# GPSDO.net
KiCad netlist of a schematic drawn in Altium Designer
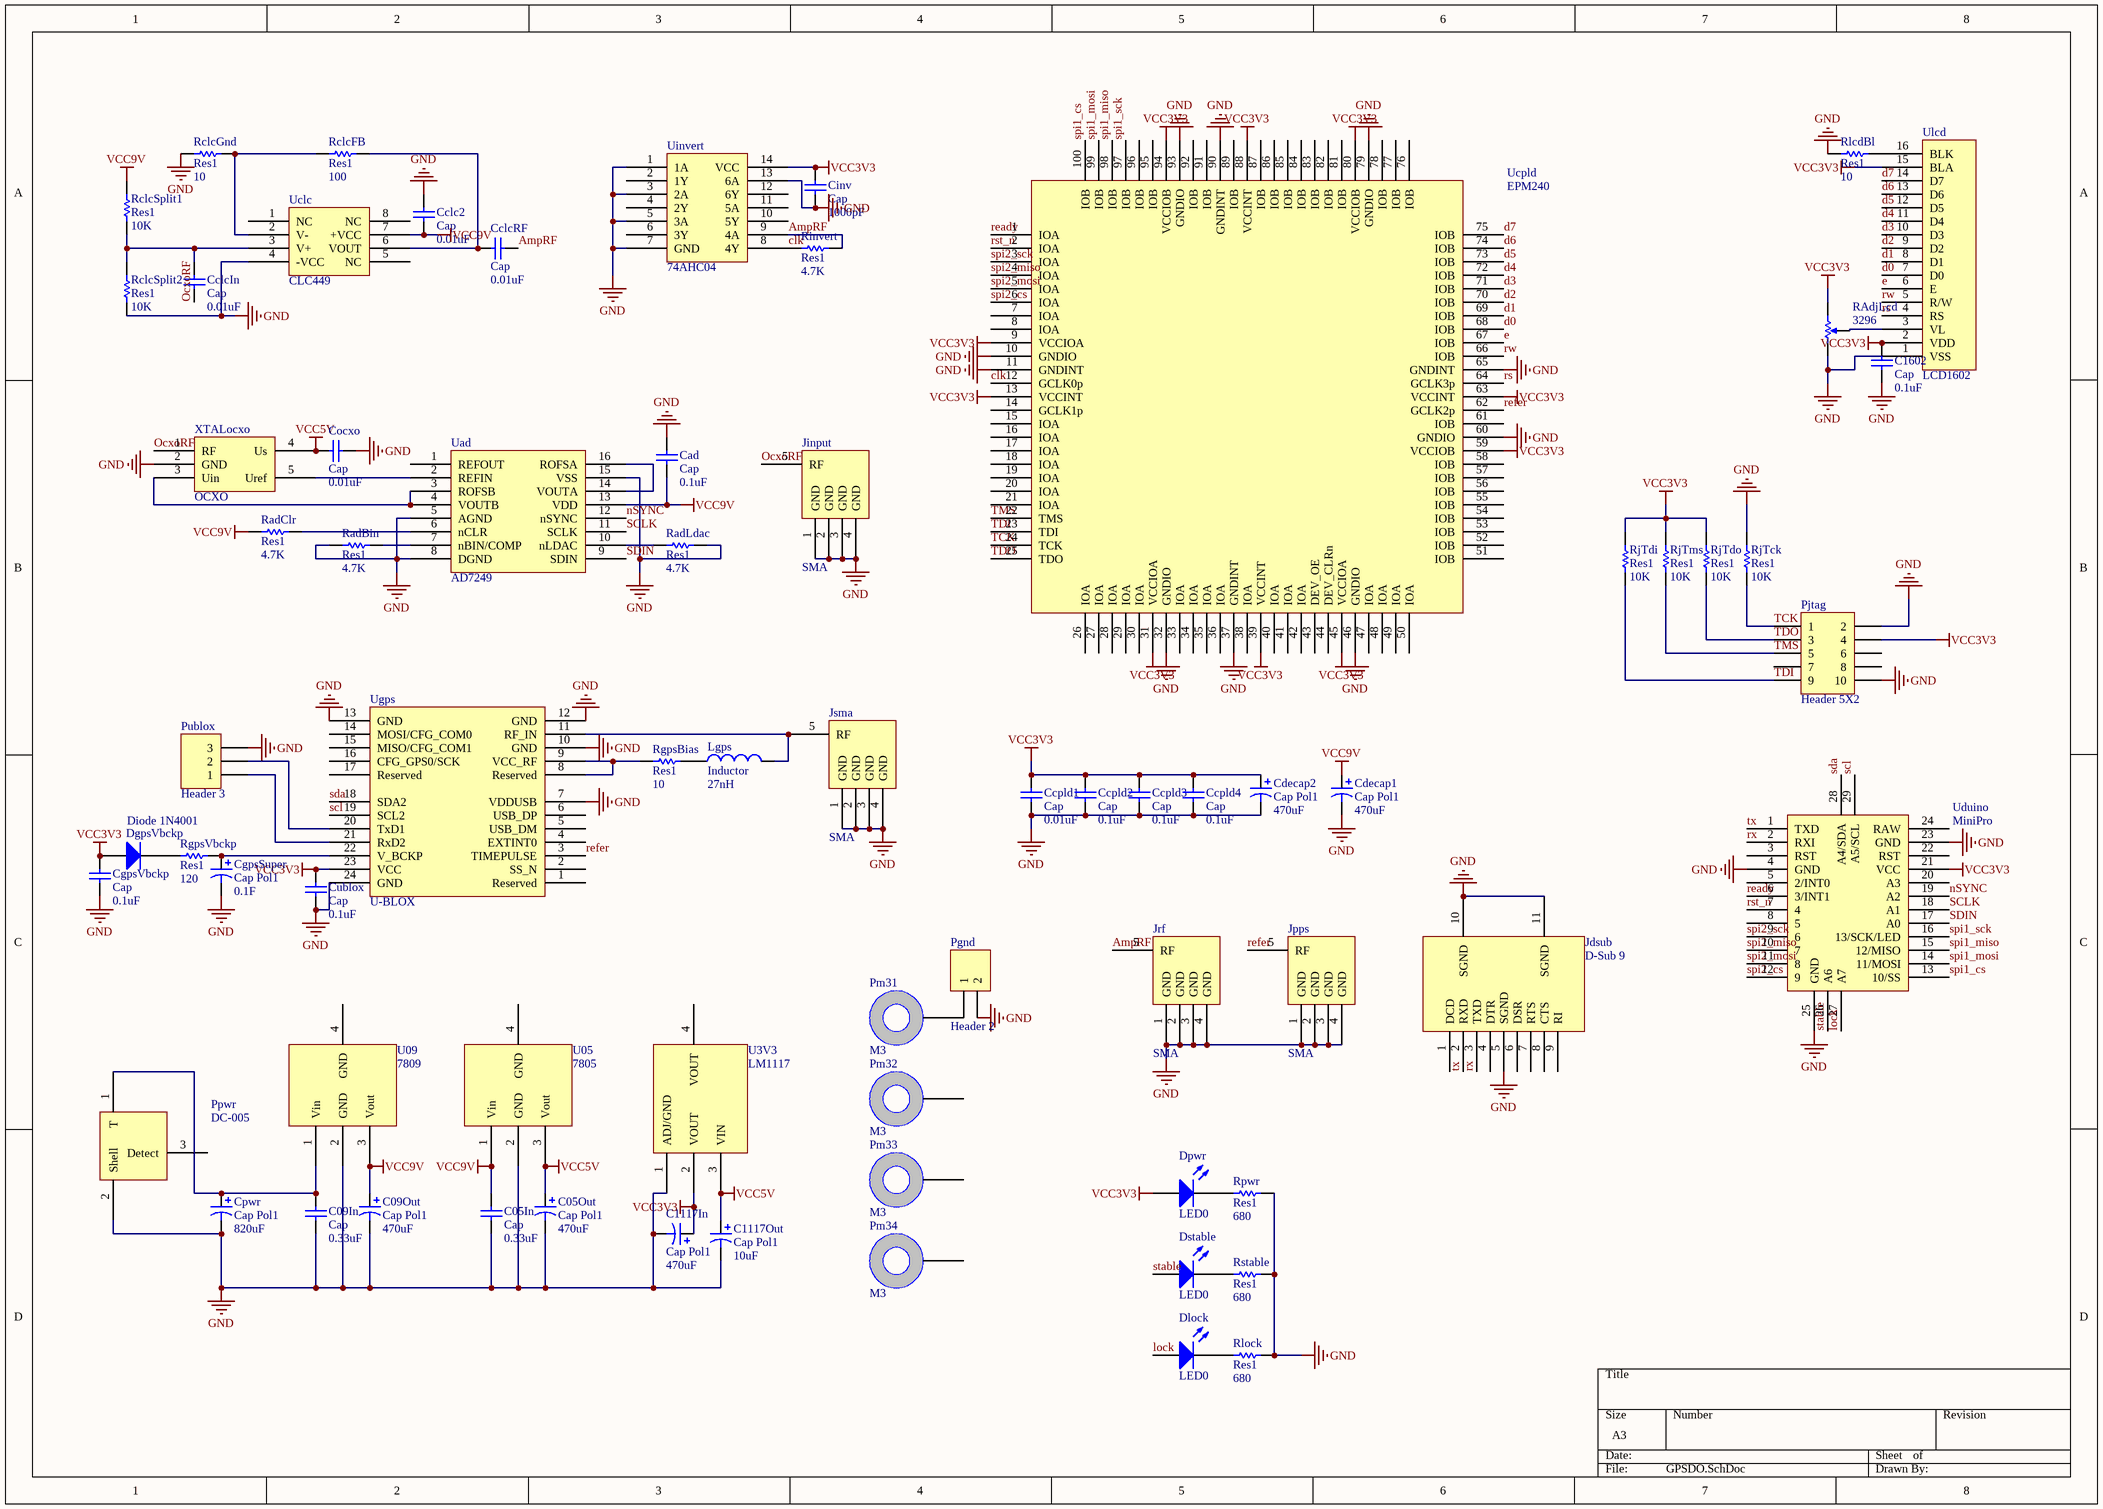
[diagram p0: GPSDO.SchDoc]

(export (version "E")
  (design (tool "Eeschema 10.0.6"))
  (components
    (comp (ref "C05In")
      (value "Cap")
      (footprint "ERO MKC1858 0.33uF/63V")
      (description "Capacitor")
      (fields (field (name "ALTIUM_VALUE") "0.33uF") (field (name "PUBLISHER") "Altium Limited"))
      (libsource (lib "Miscellaneous Devices") (part "Cap"))
    )
    (comp (ref "C05Out")
      (value "Cap Pol1")
      (footprint "SANYO SEP 560uF 10V")
      (description "Polarized Capacitor (Radial)")
      (fields (field (name "ALTIUM_VALUE") "470uF") (field (name "PUBLISHER") "Altium Limited"))
      (libsource (lib "Miscellaneous Devices") (part "Cap Pol1"))
    )
    (comp (ref "C09In")
      (value "Cap")
      (footprint "ERO MKC1858 0.33uF/63V")
      (description "Capacitor")
      (fields (field (name "ALTIUM_VALUE") "0.33uF") (field (name "PUBLISHER") "Altium Limited"))
      (libsource (lib "Miscellaneous Devices") (part "Cap"))
    )
    (comp (ref "C09Out")
      (value "Cap Pol1")
      (footprint "SANYO SEP 560uF 10V")
      (description "Polarized Capacitor (Radial)")
      (fields (field (name "ALTIUM_VALUE") "470uF") (field (name "PUBLISHER") "Altium Limited"))
      (libsource (lib "Miscellaneous Devices") (part "Cap Pol1"))
    )
    (comp (ref "C1117In")
      (value "Cap Pol1")
      (footprint "SANYO SEP 560uF 10V")
      (description "Polarized Capacitor (Radial)")
      (fields (field (name "ALTIUM_VALUE") "470uF") (field (name "PUBLISHER") "Altium Limited"))
      (libsource (lib "Miscellaneous Devices") (part "Cap Pol1"))
    )
    (comp (ref "C1117Out")
      (value "Cap Pol1")
      (footprint "Nichicon FW 10uF 100V")
      (description "Polarized Capacitor (Radial)")
      (fields (field (name "ALTIUM_VALUE") "10uF") (field (name "PUBLISHER") "Altium Limited"))
      (libsource (lib "Miscellaneous Devices") (part "Cap Pol1"))
    )
    (comp (ref "C1602")
      (value "Cap")
      (footprint "BC MKT370 0.1uF/63V")
      (description "Capacitor")
      (fields (field (name "ALTIUM_VALUE") "0.1uF") (field (name "PUBLISHER") "Altium Limited"))
      (libsource (lib "Miscellaneous Devices") (part "Cap"))
    )
    (comp (ref "Cad")
      (value "Cap")
      (footprint "BC MKT370 0.1uF/63V")
      (description "Capacitor")
      (fields (field (name "ALTIUM_VALUE") "0.1uF") (field (name "PUBLISHER") "Altium Limited"))
      (libsource (lib "Miscellaneous Devices") (part "Cap"))
    )
    (comp (ref "Cclc2")
      (value "Cap")
      (footprint "BC MKT370 0.1uF/63V")
      (description "Capacitor")
      (fields (field (name "ALTIUM_VALUE") "0.01uF") (field (name "PUBLISHER") "Altium Limited"))
      (libsource (lib "Miscellaneous Devices") (part "Cap"))
    )
    (comp (ref "CclcIn")
      (value "Cap")
      (footprint "0805.Cap.L")
      (description "Capacitor")
      (fields (field (name "ALTIUM_VALUE") "0.01uF") (field (name "PUBLISHER") "Altium Limited"))
      (libsource (lib "Miscellaneous Devices") (part "Cap"))
    )
    (comp (ref "CclcRF")
      (value "Cap")
      (footprint "0805.Cap.L")
      (description "Capacitor")
      (fields (field (name "ALTIUM_VALUE") "0.01uF") (field (name "PUBLISHER") "Altium Limited"))
      (libsource (lib "Miscellaneous Devices") (part "Cap"))
    )
    (comp (ref "Ccpld1")
      (value "Cap")
      (footprint "BC MKT370 0.1uF/63V")
      (description "Capacitor")
      (fields (field (name "ALTIUM_VALUE") "0.01uF") (field (name "PUBLISHER") "Altium Limited"))
      (libsource (lib "Miscellaneous Devices") (part "Cap"))
    )
    (comp (ref "Ccpld2")
      (value "Cap")
      (footprint "BC MKT370 0.1uF/63V")
      (description "Capacitor")
      (fields (field (name "ALTIUM_VALUE") "0.1uF") (field (name "PUBLISHER") "Altium Limited"))
      (libsource (lib "Miscellaneous Devices") (part "Cap"))
    )
    (comp (ref "Ccpld3")
      (value "Cap")
      (footprint "BC MKT370 0.1uF/63V")
      (description "Capacitor")
      (fields (field (name "ALTIUM_VALUE") "0.1uF") (field (name "PUBLISHER") "Altium Limited"))
      (libsource (lib "Miscellaneous Devices") (part "Cap"))
    )
    (comp (ref "Ccpld4")
      (value "Cap")
      (footprint "BC MKT370 0.1uF/63V")
      (description "Capacitor")
      (fields (field (name "ALTIUM_VALUE") "0.1uF") (field (name "PUBLISHER") "Altium Limited"))
      (libsource (lib "Miscellaneous Devices") (part "Cap"))
    )
    (comp (ref "Cdecap1")
      (value "Cap Pol1")
      (footprint "SANYO SEP 560uF 10V")
      (description "Polarized Capacitor (Radial)")
      (fields (field (name "ALTIUM_VALUE") "470uF") (field (name "PUBLISHER") "Altium Limited"))
      (libsource (lib "Miscellaneous Devices") (part "Cap Pol1"))
    )
    (comp (ref "Cdecap2")
      (value "Cap Pol1")
      (footprint "SANYO SEP 560uF 10V")
      (description "Polarized Capacitor (Radial)")
      (fields (field (name "ALTIUM_VALUE") "470uF") (field (name "PUBLISHER") "Altium Limited"))
      (libsource (lib "Miscellaneous Devices") (part "Cap Pol1"))
    )
    (comp (ref "CgpsSuper")
      (value "Cap Pol1")
      (footprint "Panasonic SD 0.1F / 5.5V")
      (description "Polarized Capacitor (Radial)")
      (fields (field (name "ALTIUM_VALUE") "0.1F") (field (name "PUBLISHER") "Altium Limited"))
      (libsource (lib "Miscellaneous Devices") (part "Cap Pol1"))
    )
    (comp (ref "CgpsVbckp")
      (value "Cap")
      (footprint "BC MKT370 0.1uF/63V")
      (description "Capacitor")
      (fields (field (name "ALTIUM_VALUE") "0.1uF") (field (name "PUBLISHER") "Altium Limited"))
      (libsource (lib "Miscellaneous Devices") (part "Cap"))
    )
    (comp (ref "Cinv")
      (value "Cap")
      (footprint "0805.Cap.L")
      (description "Capacitor")
      (fields (field (name "ALTIUM_VALUE") "1000pF") (field (name "PUBLISHER") "Altium Limited"))
      (libsource (lib "Miscellaneous Devices") (part "Cap"))
    )
    (comp (ref "Cocxo")
      (value "Cap")
      (footprint "BC MKT370 0.1uF/63V")
      (description "Capacitor")
      (fields (field (name "ALTIUM_VALUE") "0.01uF") (field (name "PUBLISHER") "Altium Limited"))
      (libsource (lib "Miscellaneous Devices") (part "Cap"))
    )
    (comp (ref "Cpwr")
      (value "Cap Pol1")
      (footprint "NCC LXZ 820uF 25V")
      (description "Polarized Capacitor (Radial)")
      (fields (field (name "ALTIUM_VALUE") "820uF") (field (name "PUBLISHER") "Altium Limited"))
      (libsource (lib "Miscellaneous Devices") (part "Cap Pol1"))
    )
    (comp (ref "Cublox")
      (value "Cap")
      (footprint "BC MKT370 0.1uF/63V")
      (description "Capacitor")
      (fields (field (name "ALTIUM_VALUE") "0.1uF") (field (name "PUBLISHER") "Altium Limited"))
      (libsource (lib "Miscellaneous Devices") (part "Cap"))
    )
    (comp (ref "DgpsVbckp")
      (value "Diode 1N4001")
      (footprint "1N4007")
      (description "1 Amp General Purpose Rectifier")
      (fields (field (name "PUBLISHER") "Altium Limited"))
      (libsource (lib "Miscellaneous Devices") (part "Diode 1N4001"))
    )
    (comp (ref "Dlock")
      (value "LED0")
      (footprint "3mm LED")
      (description "Typical INFRARED GaAs LED")
      (fields (field (name "PUBLISHER") "Altium Limited"))
      (libsource (lib "Miscellaneous Devices") (part "LED0"))
    )
    (comp (ref "Dpwr")
      (value "LED0")
      (footprint "3mm LED")
      (description "Typical INFRARED GaAs LED")
      (fields (field (name "PUBLISHER") "Altium Limited"))
      (libsource (lib "Miscellaneous Devices") (part "LED0"))
    )
    (comp (ref "Dstable")
      (value "LED0")
      (footprint "3mm LED")
      (description "Typical INFRARED GaAs LED")
      (fields (field (name "PUBLISHER") "Altium Limited"))
      (libsource (lib "Miscellaneous Devices") (part "LED0"))
    )
    (comp (ref "Jdsub") (value "D-Sub 9") (footprint "DSUB-9") (libsource (lib "Connector") (part "D-Sub 9")))
    (comp (ref "Jinput") (value "SMA") (footprint "SMA") (libsource (lib "Connector") (part "SMA")))
    (comp (ref "Jpps") (value "SMA") (footprint "SMA") (libsource (lib "Connector") (part "SMA")))
    (comp (ref "Jrf") (value "SMA") (footprint "SMA") (libsource (lib "Connector") (part "SMA")))
    (comp (ref "Jsma") (value "SMA") (footprint "SMA") (libsource (lib "Connector") (part "SMA")))
    (comp (ref "Lgps")
      (value "Inductor")
      (footprint "0805.L.L")
      (fields (field (name "ALTIUM_VALUE") "27nH") (field (name "PUBLISHER") "Altium Limited"))
      (libsource (lib "Miscellaneous Devices") (part "Inductor"))
    )
    (comp (ref "Pgnd")
      (value "Header 2")
      (footprint "HDR1X2")
      (description "Header, 2-Pin")
      (fields (field (name "PUBLISHER") "Altium Limited"))
      (libsource (lib "Miscellaneous Connectors") (part "Header 2"))
    )
    (comp (ref "Pjtag")
      (value "Header 5X2")
      (footprint "DC3 2.54mm 10P")
      (description "Header, 5-Pin, Dual row")
      (fields (field (name "PUBLISHER") "Altium Limited"))
      (libsource (lib "Miscellaneous Connectors") (part "Header 5X2"))
    )
    (comp (ref "Pm31")
      (value "M3")
      (footprint "M3 Screw Mount")
      (description "M3 screw mount, hole d: 3.5mm")
      (libsource (lib "TPA6120A2") (part "M3 Screw Mount"))
    )
    (comp (ref "Pm32")
      (value "M3")
      (footprint "M3 Screw Mount")
      (description "M3 screw mount, hole d: 3.5mm")
      (libsource (lib "TPA6120A2") (part "M3 Screw Mount"))
    )
    (comp (ref "Pm33")
      (value "M3")
      (footprint "M3 Screw Mount")
      (description "M3 screw mount, hole d: 3.5mm")
      (libsource (lib "TPA6120A2") (part "M3 Screw Mount"))
    )
    (comp (ref "Pm34")
      (value "M3")
      (footprint "M3 Screw Mount")
      (description "M3 screw mount, hole d: 3.5mm")
      (libsource (lib "TPA6120A2") (part "M3 Screw Mount"))
    )
    (comp (ref "Ppwr") (value "DC-005") (footprint "DC-005") (libsource (lib "Connector") (part "DC-005")))
    (comp (ref "Publox")
      (value "Header 3")
      (footprint "HDR1X3")
      (description "Header, 3-Pin")
      (fields (field (name "PUBLISHER") "Altium Limited"))
      (libsource (lib "Miscellaneous Connectors") (part "Header 3"))
    )
    (comp (ref "RadBin")
      (value "Res1")
      (footprint "RJ24")
      (description "Resistor")
      (fields (field (name "ALTIUM_VALUE") "4.7K") (field (name "PUBLISHER") "Altium Limited"))
      (libsource (lib "Miscellaneous Devices") (part "Res1"))
    )
    (comp (ref "RadClr")
      (value "Res1")
      (footprint "RJ24")
      (description "Resistor")
      (fields (field (name "ALTIUM_VALUE") "4.7K") (field (name "PUBLISHER") "Altium Limited"))
      (libsource (lib "Miscellaneous Devices") (part "Res1"))
    )
    (comp (ref "RAdjLcd")
      (value "3296")
      (footprint "3296W")
      (description "3296 - 3/8\" Square Trimming Potentiometer")
      (libsource (lib "DAC") (part "Trimming Potentiometer"))
    )
    (comp (ref "RadLdac")
      (value "Res1")
      (footprint "RJ24")
      (description "Resistor")
      (fields (field (name "ALTIUM_VALUE") "4.7K") (field (name "PUBLISHER") "Altium Limited"))
      (libsource (lib "Miscellaneous Devices") (part "Res1"))
    )
    (comp (ref "RclcFB")
      (value "Res1")
      (footprint "0805.Res.L")
      (description "Resistor")
      (fields (field (name "ALTIUM_VALUE") "100") (field (name "PUBLISHER") "Altium Limited"))
      (libsource (lib "Miscellaneous Devices") (part "Res1"))
    )
    (comp (ref "RclcGnd")
      (value "Res1")
      (footprint "0805.Res.L")
      (description "Resistor")
      (fields (field (name "ALTIUM_VALUE") "10") (field (name "PUBLISHER") "Altium Limited"))
      (libsource (lib "Miscellaneous Devices") (part "Res1"))
    )
    (comp (ref "RclcSplit1")
      (value "Res1")
      (footprint "0805.Res.L")
      (description "Resistor")
      (fields (field (name "ALTIUM_VALUE") "10K") (field (name "PUBLISHER") "Altium Limited"))
      (libsource (lib "Miscellaneous Devices") (part "Res1"))
    )
    (comp (ref "RclcSplit2")
      (value "Res1")
      (footprint "0805.Res.L")
      (description "Resistor")
      (fields (field (name "ALTIUM_VALUE") "10K") (field (name "PUBLISHER") "Altium Limited"))
      (libsource (lib "Miscellaneous Devices") (part "Res1"))
    )
    (comp (ref "RgpsBias")
      (value "Res1")
      (footprint "0805.Res.L")
      (description "Resistor")
      (fields (field (name "ALTIUM_VALUE") "10") (field (name "PUBLISHER") "Altium Limited"))
      (libsource (lib "Miscellaneous Devices") (part "Res1"))
    )
    (comp (ref "RgpsVbckp")
      (value "Res1")
      (footprint "RJ24")
      (description "Resistor")
      (fields (field (name "ALTIUM_VALUE") "120") (field (name "PUBLISHER") "Altium Limited"))
      (libsource (lib "Miscellaneous Devices") (part "Res1"))
    )
    (comp (ref "Rinvert")
      (value "Res1")
      (footprint "0805.Res.L")
      (description "Resistor")
      (fields (field (name "ALTIUM_VALUE") "4.7K") (field (name "PUBLISHER") "Altium Limited"))
      (libsource (lib "Miscellaneous Devices") (part "Res1"))
    )
    (comp (ref "RjTck")
      (value "Res1")
      (footprint "RJ24")
      (description "Resistor")
      (fields (field (name "ALTIUM_VALUE") "10K") (field (name "PUBLISHER") "Altium Limited"))
      (libsource (lib "Miscellaneous Devices") (part "Res1"))
    )
    (comp (ref "RjTdi")
      (value "Res1")
      (footprint "RJ24")
      (description "Resistor")
      (fields (field (name "ALTIUM_VALUE") "10K") (field (name "PUBLISHER") "Altium Limited"))
      (libsource (lib "Miscellaneous Devices") (part "Res1"))
    )
    (comp (ref "RjTdo")
      (value "Res1")
      (footprint "RJ24")
      (description "Resistor")
      (fields (field (name "ALTIUM_VALUE") "10K") (field (name "PUBLISHER") "Altium Limited"))
      (libsource (lib "Miscellaneous Devices") (part "Res1"))
    )
    (comp (ref "RjTms")
      (value "Res1")
      (footprint "RJ24")
      (description "Resistor")
      (fields (field (name "ALTIUM_VALUE") "10K") (field (name "PUBLISHER") "Altium Limited"))
      (libsource (lib "Miscellaneous Devices") (part "Res1"))
    )
    (comp (ref "RlcdBl")
      (value "Res1")
      (footprint "RJ24")
      (description "Resistor")
      (fields (field (name "ALTIUM_VALUE") "10") (field (name "PUBLISHER") "Altium Limited"))
      (libsource (lib "Miscellaneous Devices") (part "Res1"))
    )
    (comp (ref "Rlock")
      (value "Res1")
      (footprint "RJ24")
      (description "Resistor")
      (fields (field (name "ALTIUM_VALUE") "680") (field (name "PUBLISHER") "Altium Limited"))
      (libsource (lib "Miscellaneous Devices") (part "Res1"))
    )
    (comp (ref "Rpwr")
      (value "Res1")
      (footprint "RJ24")
      (description "Resistor")
      (fields (field (name "ALTIUM_VALUE") "680") (field (name "PUBLISHER") "Altium Limited"))
      (libsource (lib "Miscellaneous Devices") (part "Res1"))
    )
    (comp (ref "Rstable")
      (value "Res1")
      (footprint "RJ24")
      (description "Resistor")
      (fields (field (name "ALTIUM_VALUE") "680") (field (name "PUBLISHER") "Altium Limited"))
      (libsource (lib "Miscellaneous Devices") (part "Res1"))
    )
    (comp (ref "U3V3")
      (value "LM1117")
      (footprint "LM1117 SOT-223")
      (description "LM1117-N/LM1117I 800mA Low-Dropout Linear Regulator")
      (libsource (lib "Power") (part "LM1117"))
    )
    (comp (ref "U05")
      (value "7805")
      (footprint "MC7805")
      (description "1.0 A Positive Voltage  Regulators")
      (libsource (lib "Power") (part "MC7805"))
    )
    (comp (ref "U09")
      (value "7809")
      (footprint "MC7805")
      (description "1.0 A Positive Voltage  Regulators")
      (libsource (lib "Power") (part "MC7805"))
    )
    (comp (ref "Uad")
      (value "AD7249")
      (footprint "AD7249 SOIC-16")
      (description "LC2MOS Dual 12-Bit Serial DACPORT")
      (libsource (lib "Chip") (part "AD7249"))
    )
    (comp (ref "Uclc")
      (value "CLC449")
      (footprint "CLC449 SOIC-8")
      (description "1.1GHz Ultra Wideband Monolithic Op Amp")
      (libsource (lib "Chip") (part "CLC449"))
    )
    (comp (ref "Ucpld")
      (value "EPM240")
      (footprint "EPM240/570 TQFP-100")
      (description "Altera Max II CPLD")
      (libsource (lib "Chip") (part "EPM240"))
    )
    (comp (ref "Uduino")
      (value "MiniPro")
      (footprint "DIP24 - Arduino")
      (description "Microcontroller board based on the ATmega328P")
      (libsource (lib "CS4398") (part "ArduinoMiniPro"))
    )
    (comp (ref "Ugps")
      (value "U-BLOX")
      (footprint "NEO-GPS")
      (description "u-blox 6 GPS Modules")
      (libsource (lib "Module") (part "NEO-GPS"))
    )
    (comp (ref "Uinvert")
      (value "74AHC04")
      (footprint "74AHC04 SOP-14")
      (description "hex inverter")
      (libsource (lib "Chip") (part "74AHC04"))
    )
    (comp (ref "Ulcd") (value "LCD1602") (footprint "LCD1602") (libsource (lib "Module") (part "LCD1602")))
    (comp (ref "XTALocxo") (value "OCXO") (footprint "MV85") (libsource (lib "Chip") (part "OCXO")))
  )
  (nets
    (net (code "1") (name "/AmpRF") (class "Default")
      (node (ref "CclcRF") (pin "2") (pinfunction "2_2") (pintype "passive"))
      (node (ref "Jrf") (pin "5") (pinfunction "RF_5") (pintype "passive"))
      (node (ref "Rinvert") (pin "2") (pinfunction "2_2") (pintype "passive"))
      (node (ref "Uinvert") (pin "9") (pinfunction "4A_9") (pintype "passive"))
    )
    (net (code "2") (name "/OcxoRF") (class "Default")
      (node (ref "CclcIn") (pin "1") (pinfunction "1_1") (pintype "passive"))
      (node (ref "Jinput") (pin "5") (pinfunction "RF_5") (pintype "passive"))
      (node (ref "XTALocxo") (pin "1") (pinfunction "RF_1") (pintype "passive"))
    )
    (net (code "3") (name "/SCLK") (class "Default")
      (node (ref "Uad") (pin "11") (pinfunction "SCLK_11") (pintype "passive"))
      (node (ref "Uduino") (pin "18") (pinfunction "A1_18") (pintype "passive"))
    )
    (net (code "4") (name "/SDIN") (class "Default")
      (node (ref "Uad") (pin "9") (pinfunction "SDIN_9") (pintype "passive"))
      (node (ref "Uduino") (pin "17") (pinfunction "A0_17") (pintype "passive"))
    )
    (net (code "5") (name "/TCK") (class "Default")
      (node (ref "Pjtag") (pin "1") (pinfunction "1_1") (pintype "passive"))
      (node (ref "RjTck") (pin "1") (pinfunction "1_1") (pintype "passive"))
      (node (ref "Ucpld") (pin "24") (pinfunction "TCK_24") (pintype "passive"))
    )
    (net (code "6") (name "/TDI") (class "Default")
      (node (ref "Pjtag") (pin "9") (pinfunction "9_9") (pintype "passive"))
      (node (ref "RjTdi") (pin "1") (pinfunction "1_1") (pintype "passive"))
      (node (ref "Ucpld") (pin "23") (pinfunction "TDI_23") (pintype "passive"))
    )
    (net (code "7") (name "/TDO") (class "Default")
      (node (ref "Pjtag") (pin "3") (pinfunction "3_3") (pintype "passive"))
      (node (ref "RjTdo") (pin "1") (pinfunction "1_1") (pintype "passive"))
      (node (ref "Ucpld") (pin "25") (pinfunction "TDO_25") (pintype "passive"))
    )
    (net (code "8") (name "/TMS") (class "Default")
      (node (ref "Pjtag") (pin "5") (pinfunction "5_5") (pintype "passive"))
      (node (ref "RjTms") (pin "1") (pinfunction "1_1") (pintype "passive"))
      (node (ref "Ucpld") (pin "22") (pinfunction "TMS_22") (pintype "passive"))
    )
    (net (code "9") (name "/clk") (class "Default")
      (node (ref "Rinvert") (pin "1") (pinfunction "1_1") (pintype "passive"))
      (node (ref "Ucpld") (pin "12") (pinfunction "GCLK0p_12") (pintype "passive"))
      (node (ref "Uinvert") (pin "8") (pinfunction "4Y_8") (pintype "passive"))
    )
    (net (code "10") (name "/d0") (class "Default")
      (node (ref "Ucpld") (pin "68") (pinfunction "IOB_68") (pintype "passive"))
      (node (ref "Ulcd") (pin "7") (pinfunction "D0_7") (pintype "passive"))
    )
    (net (code "11") (name "/d1") (class "Default")
      (node (ref "Ucpld") (pin "69") (pinfunction "IOB_69") (pintype "passive"))
      (node (ref "Ulcd") (pin "8") (pinfunction "D1_8") (pintype "passive"))
    )
    (net (code "12") (name "/d2") (class "Default")
      (node (ref "Ucpld") (pin "70") (pinfunction "IOB_70") (pintype "passive"))
      (node (ref "Ulcd") (pin "9") (pinfunction "D2_9") (pintype "passive"))
    )
    (net (code "13") (name "/d3") (class "Default")
      (node (ref "Ucpld") (pin "71") (pinfunction "IOB_71") (pintype "passive"))
      (node (ref "Ulcd") (pin "10") (pinfunction "D3_10") (pintype "passive"))
    )
    (net (code "14") (name "/d4") (class "Default")
      (node (ref "Ucpld") (pin "72") (pinfunction "IOB_72") (pintype "passive"))
      (node (ref "Ulcd") (pin "11") (pinfunction "D4_11") (pintype "passive"))
    )
    (net (code "15") (name "/d5") (class "Default")
      (node (ref "Ucpld") (pin "73") (pinfunction "IOB_73") (pintype "passive"))
      (node (ref "Ulcd") (pin "12") (pinfunction "D5_12") (pintype "passive"))
    )
    (net (code "16") (name "/d6") (class "Default")
      (node (ref "Ucpld") (pin "74") (pinfunction "IOB_74") (pintype "passive"))
      (node (ref "Ulcd") (pin "13") (pinfunction "D6_13") (pintype "passive"))
    )
    (net (code "17") (name "/d7") (class "Default")
      (node (ref "Ucpld") (pin "75") (pinfunction "IOB_75") (pintype "passive"))
      (node (ref "Ulcd") (pin "14") (pinfunction "D7_14") (pintype "passive"))
    )
    (net (code "18") (name "/e") (class "Default")
      (node (ref "Ucpld") (pin "67") (pinfunction "IOB_67") (pintype "passive"))
      (node (ref "Ulcd") (pin "6") (pinfunction "E_6") (pintype "passive"))
    )
    (net (code "19") (name "/lock") (class "Default")
      (node (ref "Dlock") (pin "1") (pinfunction "A_1") (pintype "passive"))
      (node (ref "Uduino") (pin "27") (pinfunction "A7_27") (pintype "passive"))
    )
    (net (code "20") (name "/nSYNC") (class "Default")
      (node (ref "Uad") (pin "12") (pinfunction "nSYNC_12") (pintype "passive"))
      (node (ref "Uduino") (pin "19") (pinfunction "A2_19") (pintype "passive"))
    )
    (net (code "21") (name "/ready") (class "Default")
      (node (ref "Ucpld") (pin "1") (pinfunction "IOA_1") (pintype "passive"))
      (node (ref "Uduino") (pin "6") (pinfunction "3/INT1_6") (pintype "passive"))
    )
    (net (code "22") (name "/refer") (class "Default")
      (node (ref "Jpps") (pin "5") (pinfunction "RF_5") (pintype "passive"))
      (node (ref "Ucpld") (pin "62") (pinfunction "GCLK2p_62") (pintype "passive"))
      (node (ref "Ugps") (pin "3") (pinfunction "TIMEPULSE_3") (pintype "passive"))
    )
    (net (code "23") (name "/rs") (class "Default")
      (node (ref "Ucpld") (pin "64") (pinfunction "GCLK3p_64") (pintype "passive"))
      (node (ref "Ulcd") (pin "4") (pinfunction "RS_4") (pintype "passive"))
    )
    (net (code "24") (name "/rst_n") (class "Default")
      (node (ref "Ucpld") (pin "2") (pinfunction "IOA_2") (pintype "passive"))
      (node (ref "Uduino") (pin "7") (pinfunction "4_7") (pintype "passive"))
    )
    (net (code "25") (name "/rw") (class "Default")
      (node (ref "Ucpld") (pin "66") (pinfunction "IOB_66") (pintype "passive"))
      (node (ref "Ulcd") (pin "5") (pinfunction "R/W_5") (pintype "passive"))
    )
    (net (code "26") (name "/rx") (class "Default")
      (node (ref "Jdsub") (pin "3") (pinfunction "TXD_3") (pintype "passive"))
      (node (ref "Uduino") (pin "2") (pinfunction "RXI_2") (pintype "passive"))
    )
    (net (code "27") (name "/scl") (class "Default")
      (node (ref "Uduino") (pin "29") (pinfunction "A5/SCL_29") (pintype "passive"))
      (node (ref "Ugps") (pin "19") (pinfunction "SCL2_19") (pintype "passive"))
    )
    (net (code "28") (name "/sda") (class "Default")
      (node (ref "Uduino") (pin "28") (pinfunction "A4/SDA_28") (pintype "passive"))
      (node (ref "Ugps") (pin "18") (pinfunction "SDA2_18") (pintype "passive"))
    )
    (net (code "29") (name "/spi1_cs") (class "Default")
      (node (ref "Ucpld") (pin "100") (pinfunction "IOB_100") (pintype "passive"))
      (node (ref "Uduino") (pin "13") (pinfunction "10/SS_13") (pintype "passive"))
    )
    (net (code "30") (name "/spi1_miso") (class "Default")
      (node (ref "Ucpld") (pin "98") (pinfunction "IOB_98") (pintype "passive"))
      (node (ref "Uduino") (pin "15") (pinfunction "12/MISO_15") (pintype "passive"))
    )
    (net (code "31") (name "/spi1_mosi") (class "Default")
      (node (ref "Ucpld") (pin "99") (pinfunction "IOB_99") (pintype "passive"))
      (node (ref "Uduino") (pin "14") (pinfunction "11/MOSI_14") (pintype "passive"))
    )
    (net (code "32") (name "/spi1_sck") (class "Default")
      (node (ref "Ucpld") (pin "97") (pinfunction "IOB_97") (pintype "passive"))
      (node (ref "Uduino") (pin "16") (pinfunction "13/SCK/LED_16") (pintype "passive"))
    )
    (net (code "33") (name "/spi2_cs") (class "Default")
      (node (ref "Ucpld") (pin "6") (pinfunction "IOA_6") (pintype "passive"))
      (node (ref "Uduino") (pin "12") (pinfunction "9_12") (pintype "passive"))
    )
    (net (code "34") (name "/spi2_miso") (class "Default")
      (node (ref "Ucpld") (pin "4") (pinfunction "IOA_4") (pintype "passive"))
      (node (ref "Uduino") (pin "10") (pinfunction "7_10") (pintype "passive"))
    )
    (net (code "35") (name "/spi2_mosi") (class "Default")
      (node (ref "Ucpld") (pin "5") (pinfunction "IOA_5") (pintype "passive"))
      (node (ref "Uduino") (pin "11") (pinfunction "8_11") (pintype "passive"))
    )
    (net (code "36") (name "/spi2_sck") (class "Default")
      (node (ref "Ucpld") (pin "3") (pinfunction "IOA_3") (pintype "passive"))
      (node (ref "Uduino") (pin "9") (pinfunction "6_9") (pintype "passive"))
    )
    (net (code "37") (name "/stable") (class "Default")
      (node (ref "Dstable") (pin "1") (pinfunction "A_1") (pintype "passive"))
      (node (ref "Uduino") (pin "26") (pinfunction "A6_26") (pintype "passive"))
    )
    (net (code "38") (name "/tx") (class "Default")
      (node (ref "Jdsub") (pin "2") (pinfunction "RXD_2") (pintype "passive"))
      (node (ref "Uduino") (pin "1") (pinfunction "TXD_1") (pintype "passive"))
    )
    (net (code "39") (name "GND") (class "Default")
      (node (ref "C05In") (pin "2") (pinfunction "2_2") (pintype "passive"))
      (node (ref "C05Out") (pin "2") (pinfunction "2_2") (pintype "passive"))
      (node (ref "C09In") (pin "1") (pinfunction "1_1") (pintype "passive"))
      (node (ref "C09Out") (pin "2") (pinfunction "2_2") (pintype "passive"))
      (node (ref "C1117In") (pin "2") (pinfunction "2_2") (pintype "passive"))
      (node (ref "C1117Out") (pin "2") (pinfunction "2_2") (pintype "passive"))
      (node (ref "C1602") (pin "1") (pinfunction "1_1") (pintype "passive"))
      (node (ref "Cad") (pin "2") (pinfunction "2_2") (pintype "passive"))
      (node (ref "Cclc2") (pin "2") (pinfunction "2_2") (pintype "passive"))
      (node (ref "Ccpld1") (pin "1") (pinfunction "1_1") (pintype "passive"))
      (node (ref "Ccpld2") (pin "1") (pinfunction "1_1") (pintype "passive"))
      (node (ref "Ccpld3") (pin "1") (pinfunction "1_1") (pintype "passive"))
      (node (ref "Ccpld4") (pin "1") (pinfunction "1_1") (pintype "passive"))
      (node (ref "Cdecap1") (pin "2") (pinfunction "2_2") (pintype "passive"))
      (node (ref "Cdecap2") (pin "2") (pinfunction "2_2") (pintype "passive"))
      (node (ref "CgpsSuper") (pin "2") (pinfunction "2_2") (pintype "passive"))
      (node (ref "CgpsVbckp") (pin "1") (pinfunction "1_1") (pintype "passive"))
      (node (ref "Cinv") (pin "1") (pinfunction "1_1") (pintype "passive"))
      (node (ref "Cocxo") (pin "2") (pinfunction "2_2") (pintype "passive"))
      (node (ref "Cpwr") (pin "2") (pinfunction "2_2") (pintype "passive"))
      (node (ref "Cublox") (pin "1") (pinfunction "1_1") (pintype "passive"))
      (node (ref "Jdsub") (pin "10") (pinfunction "SGND_10") (pintype "passive"))
      (node (ref "Jdsub") (pin "11") (pinfunction "SGND_11") (pintype "passive"))
      (node (ref "Jdsub") (pin "5") (pinfunction "SGND_5") (pintype "passive"))
      (node (ref "Jinput") (pin "1") (pinfunction "GND_1") (pintype "passive"))
      (node (ref "Jinput") (pin "2") (pinfunction "GND_2") (pintype "passive"))
      (node (ref "Jinput") (pin "3") (pinfunction "GND_3") (pintype "passive"))
      (node (ref "Jinput") (pin "4") (pinfunction "GND_4") (pintype "passive"))
      (node (ref "Jpps") (pin "1") (pinfunction "GND_1") (pintype "passive"))
      (node (ref "Jpps") (pin "2") (pinfunction "GND_2") (pintype "passive"))
      (node (ref "Jpps") (pin "3") (pinfunction "GND_3") (pintype "passive"))
      (node (ref "Jpps") (pin "4") (pinfunction "GND_4") (pintype "passive"))
      (node (ref "Jrf") (pin "1") (pinfunction "GND_1") (pintype "passive"))
      (node (ref "Jrf") (pin "2") (pinfunction "GND_2") (pintype "passive"))
      (node (ref "Jrf") (pin "3") (pinfunction "GND_3") (pintype "passive"))
      (node (ref "Jrf") (pin "4") (pinfunction "GND_4") (pintype "passive"))
      (node (ref "Jsma") (pin "1") (pinfunction "GND_1") (pintype "passive"))
      (node (ref "Jsma") (pin "2") (pinfunction "GND_2") (pintype "passive"))
      (node (ref "Jsma") (pin "3") (pinfunction "GND_3") (pintype "passive"))
      (node (ref "Jsma") (pin "4") (pinfunction "GND_4") (pintype "passive"))
      (node (ref "Pgnd") (pin "2") (pinfunction "2_2") (pintype "passive"))
      (node (ref "Pjtag") (pin "10") (pinfunction "10_10") (pintype "passive"))
      (node (ref "Pjtag") (pin "2") (pinfunction "2_2") (pintype "passive"))
      (node (ref "Ppwr") (pin "2") (pinfunction "Shell_2") (pintype "passive"))
      (node (ref "Publox") (pin "3") (pinfunction "3_3") (pintype "passive"))
      (node (ref "RAdjLcd") (pin "3") (pinfunction "CW_3") (pintype "passive"))
      (node (ref "RadBin") (pin "1") (pinfunction "1_1") (pintype "passive"))
      (node (ref "RadLdac") (pin "2") (pinfunction "2_2") (pintype "passive"))
      (node (ref "RclcGnd") (pin "1") (pinfunction "1_1") (pintype "passive"))
      (node (ref "RclcSplit2") (pin "1") (pinfunction "1_1") (pintype "passive"))
      (node (ref "RjTck") (pin "2") (pinfunction "2_2") (pintype "passive"))
      (node (ref "RlcdBl") (pin "1") (pinfunction "1_1") (pintype "passive"))
      (node (ref "Rlock") (pin "2") (pinfunction "2_2") (pintype "passive"))
      (node (ref "Rpwr") (pin "2") (pinfunction "2_2") (pintype "passive"))
      (node (ref "Rstable") (pin "2") (pinfunction "2_2") (pintype "passive"))
      (node (ref "U05") (pin "2") (pinfunction "GND_2") (pintype "passive"))
      (node (ref "U09") (pin "2") (pinfunction "GND_2") (pintype "passive"))
      (node (ref "U3V3") (pin "1") (pinfunction "ADJ/GND_1") (pintype "passive"))
      (node (ref "Uad") (pin "15") (pinfunction "VSS_15") (pintype "passive"))
      (node (ref "Uad") (pin "5") (pinfunction "AGND_5") (pintype "passive"))
      (node (ref "Uad") (pin "8") (pinfunction "DGND_8") (pintype "passive"))
      (node (ref "Uclc") (pin "4") (pinfunction "-VCC_4") (pintype "passive"))
      (node (ref "Ucpld") (pin "10") (pinfunction "GNDIO_10") (pintype "passive"))
      (node (ref "Ucpld") (pin "11") (pinfunction "GNDINT_11") (pintype "passive"))
      (node (ref "Ucpld") (pin "32") (pinfunction "GNDIO_32") (pintype "passive"))
      (node (ref "Ucpld") (pin "37") (pinfunction "GNDINT_37") (pintype "passive"))
      (node (ref "Ucpld") (pin "46") (pinfunction "GNDIO_46") (pintype "passive"))
      (node (ref "Ucpld") (pin "60") (pinfunction "GNDIO_60") (pintype "passive"))
      (node (ref "Ucpld") (pin "65") (pinfunction "GNDINT_65") (pintype "passive"))
      (node (ref "Ucpld") (pin "79") (pinfunction "GNDIO_79") (pintype "passive"))
      (node (ref "Ucpld") (pin "90") (pinfunction "GNDINT_90") (pintype "passive"))
      (node (ref "Ucpld") (pin "93") (pinfunction "GNDIO_93") (pintype "passive"))
      (node (ref "Uduino") (pin "23") (pinfunction "GND_23") (pintype "passive"))
      (node (ref "Uduino") (pin "25") (pinfunction "GND_25") (pintype "passive"))
      (node (ref "Uduino") (pin "4") (pinfunction "GND_4") (pintype "passive"))
      (node (ref "Ugps") (pin "10") (pinfunction "GND_10") (pintype "passive"))
      (node (ref "Ugps") (pin "12") (pinfunction "GND_12") (pintype "passive"))
      (node (ref "Ugps") (pin "13") (pinfunction "GND_13") (pintype "passive"))
      (node (ref "Ugps") (pin "24") (pinfunction "GND_24") (pintype "passive"))
      (node (ref "Ugps") (pin "7") (pinfunction "VDDUSB_7") (pintype "passive"))
      (node (ref "Uinvert") (pin "1") (pinfunction "1A_1") (pintype "passive"))
      (node (ref "Uinvert") (pin "13") (pinfunction "6A_13") (pintype "passive"))
      (node (ref "Uinvert") (pin "3") (pinfunction "2A_3") (pintype "passive"))
      (node (ref "Uinvert") (pin "5") (pinfunction "3A_5") (pintype "passive"))
      (node (ref "Uinvert") (pin "7") (pinfunction "GND_7") (pintype "passive"))
      (node (ref "Ulcd") (pin "1") (pinfunction "VSS_1") (pintype "passive"))
      (node (ref "XTALocxo") (pin "2") (pinfunction "GND_2") (pintype "passive"))
    )
    (net (code "40") (name "Net-(DgpsVbckp-K)") (class "Default")
      (node (ref "DgpsVbckp") (pin "2") (pinfunction "K_2") (pintype "passive"))
      (node (ref "RgpsVbckp") (pin "1") (pinfunction "1_1") (pintype "passive"))
    )
    (net (code "41") (name "Net-(Dlock-K)") (class "Default")
      (node (ref "Dlock") (pin "2") (pinfunction "K_2") (pintype "passive"))
      (node (ref "Rlock") (pin "1") (pinfunction "1_1") (pintype "passive"))
    )
    (net (code "42") (name "Net-(Dpwr-K)") (class "Default")
      (node (ref "Dpwr") (pin "2") (pinfunction "K_2") (pintype "passive"))
      (node (ref "Rpwr") (pin "1") (pinfunction "1_1") (pintype "passive"))
    )
    (net (code "43") (name "Net-(Dstable-K)") (class "Default")
      (node (ref "Dstable") (pin "2") (pinfunction "K_2") (pintype "passive"))
      (node (ref "Rstable") (pin "1") (pinfunction "1_1") (pintype "passive"))
    )
    (net (code "44") (name "Net-(Jsma-RF)") (class "Default")
      (node (ref "Jsma") (pin "5") (pinfunction "RF_5") (pintype "passive"))
      (node (ref "Lgps") (pin "2") (pinfunction "2_2") (pintype "passive"))
      (node (ref "Ugps") (pin "11") (pinfunction "RF_IN_11") (pintype "passive"))
    )
    (net (code "45") (name "Net-(Lgps-Pad1)") (class "Default")
      (node (ref "Lgps") (pin "1") (pinfunction "1_1") (pintype "passive"))
      (node (ref "RgpsBias") (pin "2") (pinfunction "2_2") (pintype "passive"))
    )
    (net (code "46") (name "Net-(Pm31-GND)") (class "Default")
      (node (ref "Pgnd") (pin "1") (pinfunction "1_1") (pintype "passive"))
      (node (ref "Pm31") (pin "1") (pinfunction "GND_1") (pintype "passive"))
    )
    (net (code "47") (name "Net-(Ppwr-T)") (class "Default")
      (node (ref "C09In") (pin "2") (pinfunction "2_2") (pintype "passive"))
      (node (ref "Cpwr") (pin "1") (pinfunction "1_1") (pintype "passive"))
      (node (ref "Ppwr") (pin "1") (pinfunction "T_1") (pintype "passive"))
      (node (ref "U09") (pin "1") (pinfunction "Vin_1") (pintype "passive"))
    )
    (net (code "48") (name "Net-(RAdjLcd-WIPER)") (class "Default")
      (node (ref "RAdjLcd") (pin "2") (pinfunction "WIPER_2") (pintype "passive"))
      (node (ref "Ulcd") (pin "3") (pinfunction "VL_3") (pintype "passive"))
    )
    (net (code "49") (name "Net-(Uad-REFIN)") (class "Default")
      (node (ref "Uad") (pin "2") (pinfunction "REFIN_2") (pintype "passive"))
      (node (ref "XTALocxo") (pin "5") (pinfunction "Uref_5") (pintype "passive"))
    )
    (net (code "50") (name "Net-(Uad-ROFSA)") (class "Default")
      (node (ref "Uad") (pin "14") (pinfunction "VOUTA_14") (pintype "passive"))
      (node (ref "Uad") (pin "16") (pinfunction "ROFSA_16") (pintype "passive"))
    )
    (net (code "51") (name "Net-(Uad-ROFSB)") (class "Default")
      (node (ref "Uad") (pin "3") (pinfunction "ROFSB_3") (pintype "passive"))
      (node (ref "Uad") (pin "4") (pinfunction "VOUTB_4") (pintype "passive"))
      (node (ref "XTALocxo") (pin "3") (pinfunction "Uin_3") (pintype "passive"))
    )
    (net (code "52") (name "Net-(Uad-nBIN{slash}COMP)") (class "Default")
      (node (ref "RadBin") (pin "2") (pinfunction "2_2") (pintype "passive"))
      (node (ref "Uad") (pin "7") (pinfunction "nBIN/COMP_7") (pintype "passive"))
    )
    (net (code "53") (name "Net-(Uad-nCLR)") (class "Default")
      (node (ref "RadClr") (pin "2") (pinfunction "2_2") (pintype "passive"))
      (node (ref "Uad") (pin "6") (pinfunction "nCLR_6") (pintype "passive"))
    )
    (net (code "54") (name "Net-(Uad-nLDAC)") (class "Default")
      (node (ref "RadLdac") (pin "1") (pinfunction "1_1") (pintype "passive"))
      (node (ref "Uad") (pin "10") (pinfunction "nLDAC_10") (pintype "passive"))
    )
    (net (code "55") (name "Net-(Uclc-V+)") (class "Default")
      (node (ref "CclcIn") (pin "2") (pinfunction "2_2") (pintype "passive"))
      (node (ref "RclcSplit1") (pin "1") (pinfunction "1_1") (pintype "passive"))
      (node (ref "RclcSplit2") (pin "2") (pinfunction "2_2") (pintype "passive"))
      (node (ref "Uclc") (pin "3") (pinfunction "V+_3") (pintype "passive"))
    )
    (net (code "56") (name "Net-(Uclc-V-)") (class "Default")
      (node (ref "RclcFB") (pin "1") (pinfunction "1_1") (pintype "passive"))
      (node (ref "RclcGnd") (pin "2") (pinfunction "2_2") (pintype "passive"))
      (node (ref "Uclc") (pin "2") (pinfunction "V-_2") (pintype "passive"))
    )
    (net (code "57") (name "Net-(Uclc-VOUT)") (class "Default")
      (node (ref "CclcRF") (pin "1") (pinfunction "1_1") (pintype "passive"))
      (node (ref "RclcFB") (pin "2") (pinfunction "2_2") (pintype "passive"))
      (node (ref "Uclc") (pin "6") (pinfunction "VOUT_6") (pintype "passive"))
    )
    (net (code "58") (name "Net-(Ugps-RxD2)") (class "Default")
      (node (ref "Publox") (pin "1") (pinfunction "1_1") (pintype "passive"))
      (node (ref "Ugps") (pin "21") (pinfunction "RxD2_21") (pintype "passive"))
    )
    (net (code "59") (name "Net-(Ugps-TxD1)") (class "Default")
      (node (ref "Publox") (pin "2") (pinfunction "2_2") (pintype "passive"))
      (node (ref "Ugps") (pin "20") (pinfunction "TxD1_20") (pintype "passive"))
    )
    (net (code "60") (name "Net-(Ugps-VCC_RF)") (class "Default")
      (node (ref "RgpsBias") (pin "1") (pinfunction "1_1") (pintype "passive"))
      (node (ref "Ugps") (pin "8") (pinfunction "Reserved_8") (pintype "passive"))
      (node (ref "Ugps") (pin "9") (pinfunction "VCC_RF_9") (pintype "passive"))
    )
    (net (code "61") (name "Net-(Ugps-V_BCKP)") (class "Default")
      (node (ref "CgpsSuper") (pin "1") (pinfunction "1_1") (pintype "passive"))
      (node (ref "RgpsVbckp") (pin "2") (pinfunction "2_2") (pintype "passive"))
      (node (ref "Ugps") (pin "22") (pinfunction "V_BCKP_22") (pintype "passive"))
    )
    (net (code "62") (name "Net-(Ulcd-BLK)") (class "Default")
      (node (ref "RlcdBl") (pin "2") (pinfunction "2_2") (pintype "passive"))
      (node (ref "Ulcd") (pin "16") (pinfunction "BLK_16") (pintype "passive"))
    )
    (net (code "63") (name "VCC3V3") (class "Default")
      (node (ref "C1117In") (pin "1") (pinfunction "1_1") (pintype "passive"))
      (node (ref "C1602") (pin "2") (pinfunction "2_2") (pintype "passive"))
      (node (ref "Ccpld1") (pin "2") (pinfunction "2_2") (pintype "passive"))
      (node (ref "Ccpld2") (pin "2") (pinfunction "2_2") (pintype "passive"))
      (node (ref "Ccpld3") (pin "2") (pinfunction "2_2") (pintype "passive"))
      (node (ref "Ccpld4") (pin "2") (pinfunction "2_2") (pintype "passive"))
      (node (ref "Cdecap2") (pin "1") (pinfunction "1_1") (pintype "passive"))
      (node (ref "CgpsVbckp") (pin "2") (pinfunction "2_2") (pintype "passive"))
      (node (ref "Cinv") (pin "2") (pinfunction "2_2") (pintype "passive"))
      (node (ref "Cublox") (pin "2") (pinfunction "2_2") (pintype "passive"))
      (node (ref "DgpsVbckp") (pin "1") (pinfunction "A_1") (pintype "passive"))
      (node (ref "Dpwr") (pin "1") (pinfunction "A_1") (pintype "passive"))
      (node (ref "Pjtag") (pin "4") (pinfunction "4_4") (pintype "passive"))
      (node (ref "RAdjLcd") (pin "1") (pinfunction "CCW_1") (pintype "passive"))
      (node (ref "RjTdi") (pin "2") (pinfunction "2_2") (pintype "passive"))
      (node (ref "RjTdo") (pin "2") (pinfunction "2_2") (pintype "passive"))
      (node (ref "RjTms") (pin "2") (pinfunction "2_2") (pintype "passive"))
      (node (ref "U3V3") (pin "2") (pinfunction "VOUT_2") (pintype "passive"))
      (node (ref "Ucpld") (pin "13") (pinfunction "VCCINT_13") (pintype "passive"))
      (node (ref "Ucpld") (pin "31") (pinfunction "VCCIOA_31") (pintype "passive"))
      (node (ref "Ucpld") (pin "39") (pinfunction "VCCINT_39") (pintype "passive"))
      (node (ref "Ucpld") (pin "45") (pinfunction "VCCIOA_45") (pintype "passive"))
      (node (ref "Ucpld") (pin "59") (pinfunction "VCCIOB_59") (pintype "passive"))
      (node (ref "Ucpld") (pin "63") (pinfunction "VCCINT_63") (pintype "passive"))
      (node (ref "Ucpld") (pin "80") (pinfunction "VCCIOB_80") (pintype "passive"))
      (node (ref "Ucpld") (pin "88") (pinfunction "VCCINT_88") (pintype "passive"))
      (node (ref "Ucpld") (pin "9") (pinfunction "VCCIOA_9") (pintype "passive"))
      (node (ref "Ucpld") (pin "94") (pinfunction "VCCIOB_94") (pintype "passive"))
      (node (ref "Uduino") (pin "21") (pinfunction "VCC_21") (pintype "passive"))
      (node (ref "Ugps") (pin "23") (pinfunction "VCC_23") (pintype "passive"))
      (node (ref "Uinvert") (pin "14") (pinfunction "VCC_14") (pintype "passive"))
      (node (ref "Ulcd") (pin "15") (pinfunction "BLA_15") (pintype "passive"))
      (node (ref "Ulcd") (pin "2") (pinfunction "VDD_2") (pintype "passive"))
    )
    (net (code "64") (name "VCC5V") (class "Default")
      (node (ref "C05Out") (pin "1") (pinfunction "1_1") (pintype "passive"))
      (node (ref "C1117Out") (pin "1") (pinfunction "1_1") (pintype "passive"))
      (node (ref "Cocxo") (pin "1") (pinfunction "1_1") (pintype "passive"))
      (node (ref "U05") (pin "3") (pinfunction "Vout_3") (pintype "passive"))
      (node (ref "U3V3") (pin "3") (pinfunction "VIN_3") (pintype "passive"))
      (node (ref "XTALocxo") (pin "4") (pinfunction "Us_4") (pintype "passive"))
    )
    (net (code "65") (name "VCC9V") (class "Default")
      (node (ref "C05In") (pin "1") (pinfunction "1_1") (pintype "passive"))
      (node (ref "C09Out") (pin "1") (pinfunction "1_1") (pintype "passive"))
      (node (ref "Cad") (pin "1") (pinfunction "1_1") (pintype "passive"))
      (node (ref "Cclc2") (pin "1") (pinfunction "1_1") (pintype "passive"))
      (node (ref "Cdecap1") (pin "1") (pinfunction "1_1") (pintype "passive"))
      (node (ref "RadClr") (pin "1") (pinfunction "1_1") (pintype "passive"))
      (node (ref "RclcSplit1") (pin "2") (pinfunction "2_2") (pintype "passive"))
      (node (ref "U05") (pin "1") (pinfunction "Vin_1") (pintype "passive"))
      (node (ref "U09") (pin "3") (pinfunction "Vout_3") (pintype "passive"))
      (node (ref "Uad") (pin "13") (pinfunction "VDD_13") (pintype "passive"))
      (node (ref "Uclc") (pin "7") (pinfunction "+VCC_7") (pintype "passive"))
    )
    (net (code "66") (name "unconnected-(Jdsub-CTS-Pad8)") (class "Default")
      (node (ref "Jdsub") (pin "8") (pinfunction "CTS_8") (pintype "passive"))
    )
    (net (code "67") (name "unconnected-(Jdsub-DCD-Pad1)") (class "Default")
      (node (ref "Jdsub") (pin "1") (pinfunction "DCD_1") (pintype "passive"))
    )
    (net (code "68") (name "unconnected-(Jdsub-DSR-Pad6)") (class "Default")
      (node (ref "Jdsub") (pin "6") (pinfunction "DSR_6") (pintype "passive"))
    )
    (net (code "69") (name "unconnected-(Jdsub-DTR-Pad4)") (class "Default")
      (node (ref "Jdsub") (pin "4") (pinfunction "DTR_4") (pintype "passive"))
    )
    (net (code "70") (name "unconnected-(Jdsub-RI-Pad9)") (class "Default")
      (node (ref "Jdsub") (pin "9") (pinfunction "RI_9") (pintype "passive"))
    )
    (net (code "71") (name "unconnected-(Jdsub-RTS-Pad7)") (class "Default")
      (node (ref "Jdsub") (pin "7") (pinfunction "RTS_7") (pintype "passive"))
    )
    (net (code "72") (name "unconnected-(Pjtag-Pad6)") (class "Default")
      (node (ref "Pjtag") (pin "6") (pinfunction "6_6") (pintype "passive"))
    )
    (net (code "73") (name "unconnected-(Pjtag-Pad7)") (class "Default")
      (node (ref "Pjtag") (pin "7") (pinfunction "7_7") (pintype "passive"))
    )
    (net (code "74") (name "unconnected-(Pjtag-Pad8)") (class "Default")
      (node (ref "Pjtag") (pin "8") (pinfunction "8_8") (pintype "passive"))
    )
    (net (code "75") (name "unconnected-(Pm32-GND-Pad1)") (class "Default")
      (node (ref "Pm32") (pin "1") (pinfunction "GND_1") (pintype "passive"))
    )
    (net (code "76") (name "unconnected-(Pm33-GND-Pad1)") (class "Default")
      (node (ref "Pm33") (pin "1") (pinfunction "GND_1") (pintype "passive"))
    )
    (net (code "77") (name "unconnected-(Pm34-GND-Pad1)") (class "Default")
      (node (ref "Pm34") (pin "1") (pinfunction "GND_1") (pintype "passive"))
    )
    (net (code "78") (name "unconnected-(Ppwr-Detect-Pad3)") (class "Default")
      (node (ref "Ppwr") (pin "3") (pinfunction "Detect_3") (pintype "passive"))
    )
    (net (code "79") (name "unconnected-(U3V3-VOUT-Pad4)") (class "Default")
      (node (ref "U3V3") (pin "4") (pinfunction "VOUT_4") (pintype "passive"))
    )
    (net (code "80") (name "unconnected-(U05-GND-Pad4)") (class "Default")
      (node (ref "U05") (pin "4") (pinfunction "GND_4") (pintype "passive"))
    )
    (net (code "81") (name "unconnected-(U09-GND-Pad4)") (class "Default")
      (node (ref "U09") (pin "4") (pinfunction "GND_4") (pintype "passive"))
    )
    (net (code "82") (name "unconnected-(Uad-REFOUT-Pad1)") (class "Default")
      (node (ref "Uad") (pin "1") (pinfunction "REFOUT_1") (pintype "passive"))
    )
    (net (code "83") (name "unconnected-(Uclc-NC-Pad1)") (class "Default")
      (node (ref "Uclc") (pin "1") (pinfunction "NC_1") (pintype "passive"))
    )
    (net (code "84") (name "unconnected-(Uclc-NC-Pad5)") (class "Default")
      (node (ref "Uclc") (pin "5") (pinfunction "NC_5") (pintype "passive"))
    )
    (net (code "85") (name "unconnected-(Uclc-NC-Pad8)") (class "Default")
      (node (ref "Uclc") (pin "8") (pinfunction "NC_8") (pintype "passive"))
    )
    (net (code "86") (name "unconnected-(Ucpld-DEV_CLRn-Pad44)") (class "Default")
      (node (ref "Ucpld") (pin "44") (pinfunction "DEV_CLRn_44") (pintype "passive"))
    )
    (net (code "87") (name "unconnected-(Ucpld-DEV_OE-Pad43)") (class "Default")
      (node (ref "Ucpld") (pin "43") (pinfunction "DEV_OE_43") (pintype "passive"))
    )
    (net (code "88") (name "unconnected-(Ucpld-GCLK1p-Pad14)") (class "Default")
      (node (ref "Ucpld") (pin "14") (pinfunction "GCLK1p_14") (pintype "passive"))
    )
    (net (code "89") (name "unconnected-(Ucpld-IOA-Pad7)") (class "Default")
      (node (ref "Ucpld") (pin "7") (pinfunction "IOA_7") (pintype "passive"))
    )
    (net (code "90") (name "unconnected-(Ucpld-IOA-Pad8)") (class "Default")
      (node (ref "Ucpld") (pin "8") (pinfunction "IOA_8") (pintype "passive"))
    )
    (net (code "91") (name "unconnected-(Ucpld-IOA-Pad15)") (class "Default")
      (node (ref "Ucpld") (pin "15") (pinfunction "IOA_15") (pintype "passive"))
    )
    (net (code "92") (name "unconnected-(Ucpld-IOA-Pad16)") (class "Default")
      (node (ref "Ucpld") (pin "16") (pinfunction "IOA_16") (pintype "passive"))
    )
    (net (code "93") (name "unconnected-(Ucpld-IOA-Pad17)") (class "Default")
      (node (ref "Ucpld") (pin "17") (pinfunction "IOA_17") (pintype "passive"))
    )
    (net (code "94") (name "unconnected-(Ucpld-IOA-Pad18)") (class "Default")
      (node (ref "Ucpld") (pin "18") (pinfunction "IOA_18") (pintype "passive"))
    )
    (net (code "95") (name "unconnected-(Ucpld-IOA-Pad19)") (class "Default")
      (node (ref "Ucpld") (pin "19") (pinfunction "IOA_19") (pintype "passive"))
    )
    (net (code "96") (name "unconnected-(Ucpld-IOA-Pad20)") (class "Default")
      (node (ref "Ucpld") (pin "20") (pinfunction "IOA_20") (pintype "passive"))
    )
    (net (code "97") (name "unconnected-(Ucpld-IOA-Pad21)") (class "Default")
      (node (ref "Ucpld") (pin "21") (pinfunction "IOA_21") (pintype "passive"))
    )
    (net (code "98") (name "unconnected-(Ucpld-IOA-Pad26)") (class "Default")
      (node (ref "Ucpld") (pin "26") (pinfunction "IOA_26") (pintype "passive"))
    )
    (net (code "99") (name "unconnected-(Ucpld-IOA-Pad27)") (class "Default")
      (node (ref "Ucpld") (pin "27") (pinfunction "IOA_27") (pintype "passive"))
    )
    (net (code "100") (name "unconnected-(Ucpld-IOA-Pad28)") (class "Default")
      (node (ref "Ucpld") (pin "28") (pinfunction "IOA_28") (pintype "passive"))
    )
    (net (code "101") (name "unconnected-(Ucpld-IOA-Pad29)") (class "Default")
      (node (ref "Ucpld") (pin "29") (pinfunction "IOA_29") (pintype "passive"))
    )
    (net (code "102") (name "unconnected-(Ucpld-IOA-Pad30)") (class "Default")
      (node (ref "Ucpld") (pin "30") (pinfunction "IOA_30") (pintype "passive"))
    )
    (net (code "103") (name "unconnected-(Ucpld-IOA-Pad33)") (class "Default")
      (node (ref "Ucpld") (pin "33") (pinfunction "IOA_33") (pintype "passive"))
    )
    (net (code "104") (name "unconnected-(Ucpld-IOA-Pad34)") (class "Default")
      (node (ref "Ucpld") (pin "34") (pinfunction "IOA_34") (pintype "passive"))
    )
    (net (code "105") (name "unconnected-(Ucpld-IOA-Pad35)") (class "Default")
      (node (ref "Ucpld") (pin "35") (pinfunction "IOA_35") (pintype "passive"))
    )
    (net (code "106") (name "unconnected-(Ucpld-IOA-Pad36)") (class "Default")
      (node (ref "Ucpld") (pin "36") (pinfunction "IOA_36") (pintype "passive"))
    )
    (net (code "107") (name "unconnected-(Ucpld-IOA-Pad38)") (class "Default")
      (node (ref "Ucpld") (pin "38") (pinfunction "IOA_38") (pintype "passive"))
    )
    (net (code "108") (name "unconnected-(Ucpld-IOA-Pad40)") (class "Default")
      (node (ref "Ucpld") (pin "40") (pinfunction "IOA_40") (pintype "passive"))
    )
    (net (code "109") (name "unconnected-(Ucpld-IOA-Pad41)") (class "Default")
      (node (ref "Ucpld") (pin "41") (pinfunction "IOA_41") (pintype "passive"))
    )
    (net (code "110") (name "unconnected-(Ucpld-IOA-Pad42)") (class "Default")
      (node (ref "Ucpld") (pin "42") (pinfunction "IOA_42") (pintype "passive"))
    )
    (net (code "111") (name "unconnected-(Ucpld-IOA-Pad47)") (class "Default")
      (node (ref "Ucpld") (pin "47") (pinfunction "IOA_47") (pintype "passive"))
    )
    (net (code "112") (name "unconnected-(Ucpld-IOA-Pad48)") (class "Default")
      (node (ref "Ucpld") (pin "48") (pinfunction "IOA_48") (pintype "passive"))
    )
    (net (code "113") (name "unconnected-(Ucpld-IOA-Pad49)") (class "Default")
      (node (ref "Ucpld") (pin "49") (pinfunction "IOA_49") (pintype "passive"))
    )
    (net (code "114") (name "unconnected-(Ucpld-IOA-Pad50)") (class "Default")
      (node (ref "Ucpld") (pin "50") (pinfunction "IOA_50") (pintype "passive"))
    )
    (net (code "115") (name "unconnected-(Ucpld-IOB-Pad51)") (class "Default")
      (node (ref "Ucpld") (pin "51") (pinfunction "IOB_51") (pintype "passive"))
    )
    (net (code "116") (name "unconnected-(Ucpld-IOB-Pad52)") (class "Default")
      (node (ref "Ucpld") (pin "52") (pinfunction "IOB_52") (pintype "passive"))
    )
    (net (code "117") (name "unconnected-(Ucpld-IOB-Pad53)") (class "Default")
      (node (ref "Ucpld") (pin "53") (pinfunction "IOB_53") (pintype "passive"))
    )
    (net (code "118") (name "unconnected-(Ucpld-IOB-Pad54)") (class "Default")
      (node (ref "Ucpld") (pin "54") (pinfunction "IOB_54") (pintype "passive"))
    )
    (net (code "119") (name "unconnected-(Ucpld-IOB-Pad55)") (class "Default")
      (node (ref "Ucpld") (pin "55") (pinfunction "IOB_55") (pintype "passive"))
    )
    (net (code "120") (name "unconnected-(Ucpld-IOB-Pad56)") (class "Default")
      (node (ref "Ucpld") (pin "56") (pinfunction "IOB_56") (pintype "passive"))
    )
    (net (code "121") (name "unconnected-(Ucpld-IOB-Pad57)") (class "Default")
      (node (ref "Ucpld") (pin "57") (pinfunction "IOB_57") (pintype "passive"))
    )
    (net (code "122") (name "unconnected-(Ucpld-IOB-Pad58)") (class "Default")
      (node (ref "Ucpld") (pin "58") (pinfunction "IOB_58") (pintype "passive"))
    )
    (net (code "123") (name "unconnected-(Ucpld-IOB-Pad61)") (class "Default")
      (node (ref "Ucpld") (pin "61") (pinfunction "IOB_61") (pintype "passive"))
    )
    (net (code "124") (name "unconnected-(Ucpld-IOB-Pad76)") (class "Default")
      (node (ref "Ucpld") (pin "76") (pinfunction "IOB_76") (pintype "passive"))
    )
    (net (code "125") (name "unconnected-(Ucpld-IOB-Pad77)") (class "Default")
      (node (ref "Ucpld") (pin "77") (pinfunction "IOB_77") (pintype "passive"))
    )
    (net (code "126") (name "unconnected-(Ucpld-IOB-Pad78)") (class "Default")
      (node (ref "Ucpld") (pin "78") (pinfunction "IOB_78") (pintype "passive"))
    )
    (net (code "127") (name "unconnected-(Ucpld-IOB-Pad81)") (class "Default")
      (node (ref "Ucpld") (pin "81") (pinfunction "IOB_81") (pintype "passive"))
    )
    (net (code "128") (name "unconnected-(Ucpld-IOB-Pad82)") (class "Default")
      (node (ref "Ucpld") (pin "82") (pinfunction "IOB_82") (pintype "passive"))
    )
    (net (code "129") (name "unconnected-(Ucpld-IOB-Pad83)") (class "Default")
      (node (ref "Ucpld") (pin "83") (pinfunction "IOB_83") (pintype "passive"))
    )
    (net (code "130") (name "unconnected-(Ucpld-IOB-Pad84)") (class "Default")
      (node (ref "Ucpld") (pin "84") (pinfunction "IOB_84") (pintype "passive"))
    )
    (net (code "131") (name "unconnected-(Ucpld-IOB-Pad85)") (class "Default")
      (node (ref "Ucpld") (pin "85") (pinfunction "IOB_85") (pintype "passive"))
    )
    (net (code "132") (name "unconnected-(Ucpld-IOB-Pad86)") (class "Default")
      (node (ref "Ucpld") (pin "86") (pinfunction "IOB_86") (pintype "passive"))
    )
    (net (code "133") (name "unconnected-(Ucpld-IOB-Pad87)") (class "Default")
      (node (ref "Ucpld") (pin "87") (pinfunction "IOB_87") (pintype "passive"))
    )
    (net (code "134") (name "unconnected-(Ucpld-IOB-Pad89)") (class "Default")
      (node (ref "Ucpld") (pin "89") (pinfunction "IOB_89") (pintype "passive"))
    )
    (net (code "135") (name "unconnected-(Ucpld-IOB-Pad91)") (class "Default")
      (node (ref "Ucpld") (pin "91") (pinfunction "IOB_91") (pintype "passive"))
    )
    (net (code "136") (name "unconnected-(Ucpld-IOB-Pad92)") (class "Default")
      (node (ref "Ucpld") (pin "92") (pinfunction "IOB_92") (pintype "passive"))
    )
    (net (code "137") (name "unconnected-(Ucpld-IOB-Pad95)") (class "Default")
      (node (ref "Ucpld") (pin "95") (pinfunction "IOB_95") (pintype "passive"))
    )
    (net (code "138") (name "unconnected-(Ucpld-IOB-Pad96)") (class "Default")
      (node (ref "Ucpld") (pin "96") (pinfunction "IOB_96") (pintype "passive"))
    )
    (net (code "139") (name "unconnected-(Uduino-2{slash}INT0-Pad5)") (class "Default")
      (node (ref "Uduino") (pin "5") (pinfunction "2/INT0_5") (pintype "passive"))
    )
    (net (code "140") (name "unconnected-(Uduino-5-Pad8)") (class "Default")
      (node (ref "Uduino") (pin "8") (pinfunction "5_8") (pintype "passive"))
    )
    (net (code "141") (name "unconnected-(Uduino-A3-Pad20)") (class "Default")
      (node (ref "Uduino") (pin "20") (pinfunction "A3_20") (pintype "passive"))
    )
    (net (code "142") (name "unconnected-(Uduino-RAW-Pad24)") (class "Default")
      (node (ref "Uduino") (pin "24") (pinfunction "RAW_24") (pintype "passive"))
    )
    (net (code "143") (name "unconnected-(Uduino-RST-Pad3)") (class "Default")
      (node (ref "Uduino") (pin "3") (pinfunction "RST_3") (pintype "passive"))
    )
    (net (code "144") (name "unconnected-(Uduino-RST-Pad22)") (class "Default")
      (node (ref "Uduino") (pin "22") (pinfunction "RST_22") (pintype "passive"))
    )
    (net (code "145") (name "unconnected-(Ugps-CFG_GPS0{slash}SCK-Pad16)") (class "Default")
      (node (ref "Ugps") (pin "16") (pinfunction "CFG_GPS0/SCK_16") (pintype "passive"))
    )
    (net (code "146") (name "unconnected-(Ugps-EXTINT0-Pad4)") (class "Default")
      (node (ref "Ugps") (pin "4") (pinfunction "EXTINT0_4") (pintype "passive"))
    )
    (net (code "147") (name "unconnected-(Ugps-MISO{slash}CFG_COM1-Pad15)") (class "Default")
      (node (ref "Ugps") (pin "15") (pinfunction "MISO/CFG_COM1_15") (pintype "passive"))
    )
    (net (code "148") (name "unconnected-(Ugps-MOSI{slash}CFG_COM0-Pad14)") (class "Default")
      (node (ref "Ugps") (pin "14") (pinfunction "MOSI/CFG_COM0_14") (pintype "passive"))
    )
    (net (code "149") (name "unconnected-(Ugps-Reserved-Pad1)") (class "Default")
      (node (ref "Ugps") (pin "1") (pinfunction "Reserved_1") (pintype "passive"))
    )
    (net (code "150") (name "unconnected-(Ugps-Reserved-Pad17)") (class "Default")
      (node (ref "Ugps") (pin "17") (pinfunction "Reserved_17") (pintype "passive"))
    )
    (net (code "151") (name "unconnected-(Ugps-SS_N-Pad2)") (class "Default")
      (node (ref "Ugps") (pin "2") (pinfunction "SS_N_2") (pintype "passive"))
    )
    (net (code "152") (name "unconnected-(Ugps-USB_DM-Pad5)") (class "Default")
      (node (ref "Ugps") (pin "5") (pinfunction "USB_DM_5") (pintype "passive"))
    )
    (net (code "153") (name "unconnected-(Ugps-USB_DP-Pad6)") (class "Default")
      (node (ref "Ugps") (pin "6") (pinfunction "USB_DP_6") (pintype "passive"))
    )
    (net (code "154") (name "unconnected-(Uinvert-1Y-Pad2)") (class "Default")
      (node (ref "Uinvert") (pin "2") (pinfunction "1Y_2") (pintype "passive"))
    )
    (net (code "155") (name "unconnected-(Uinvert-2Y-Pad4)") (class "Default")
      (node (ref "Uinvert") (pin "4") (pinfunction "2Y_4") (pintype "passive"))
    )
    (net (code "156") (name "unconnected-(Uinvert-3Y-Pad6)") (class "Default")
      (node (ref "Uinvert") (pin "6") (pinfunction "3Y_6") (pintype "passive"))
    )
    (net (code "157") (name "unconnected-(Uinvert-5A-Pad11)") (class "Default")
      (node (ref "Uinvert") (pin "11") (pinfunction "5A_11") (pintype "passive"))
    )
    (net (code "158") (name "unconnected-(Uinvert-5Y-Pad10)") (class "Default")
      (node (ref "Uinvert") (pin "10") (pinfunction "5Y_10") (pintype "passive"))
    )
    (net (code "159") (name "unconnected-(Uinvert-6Y-Pad12)") (class "Default")
      (node (ref "Uinvert") (pin "12") (pinfunction "6Y_12") (pintype "passive"))
    )
  )
)
